# Sheet1.net
KiCad netlist of a schematic drawn in Altium Designer
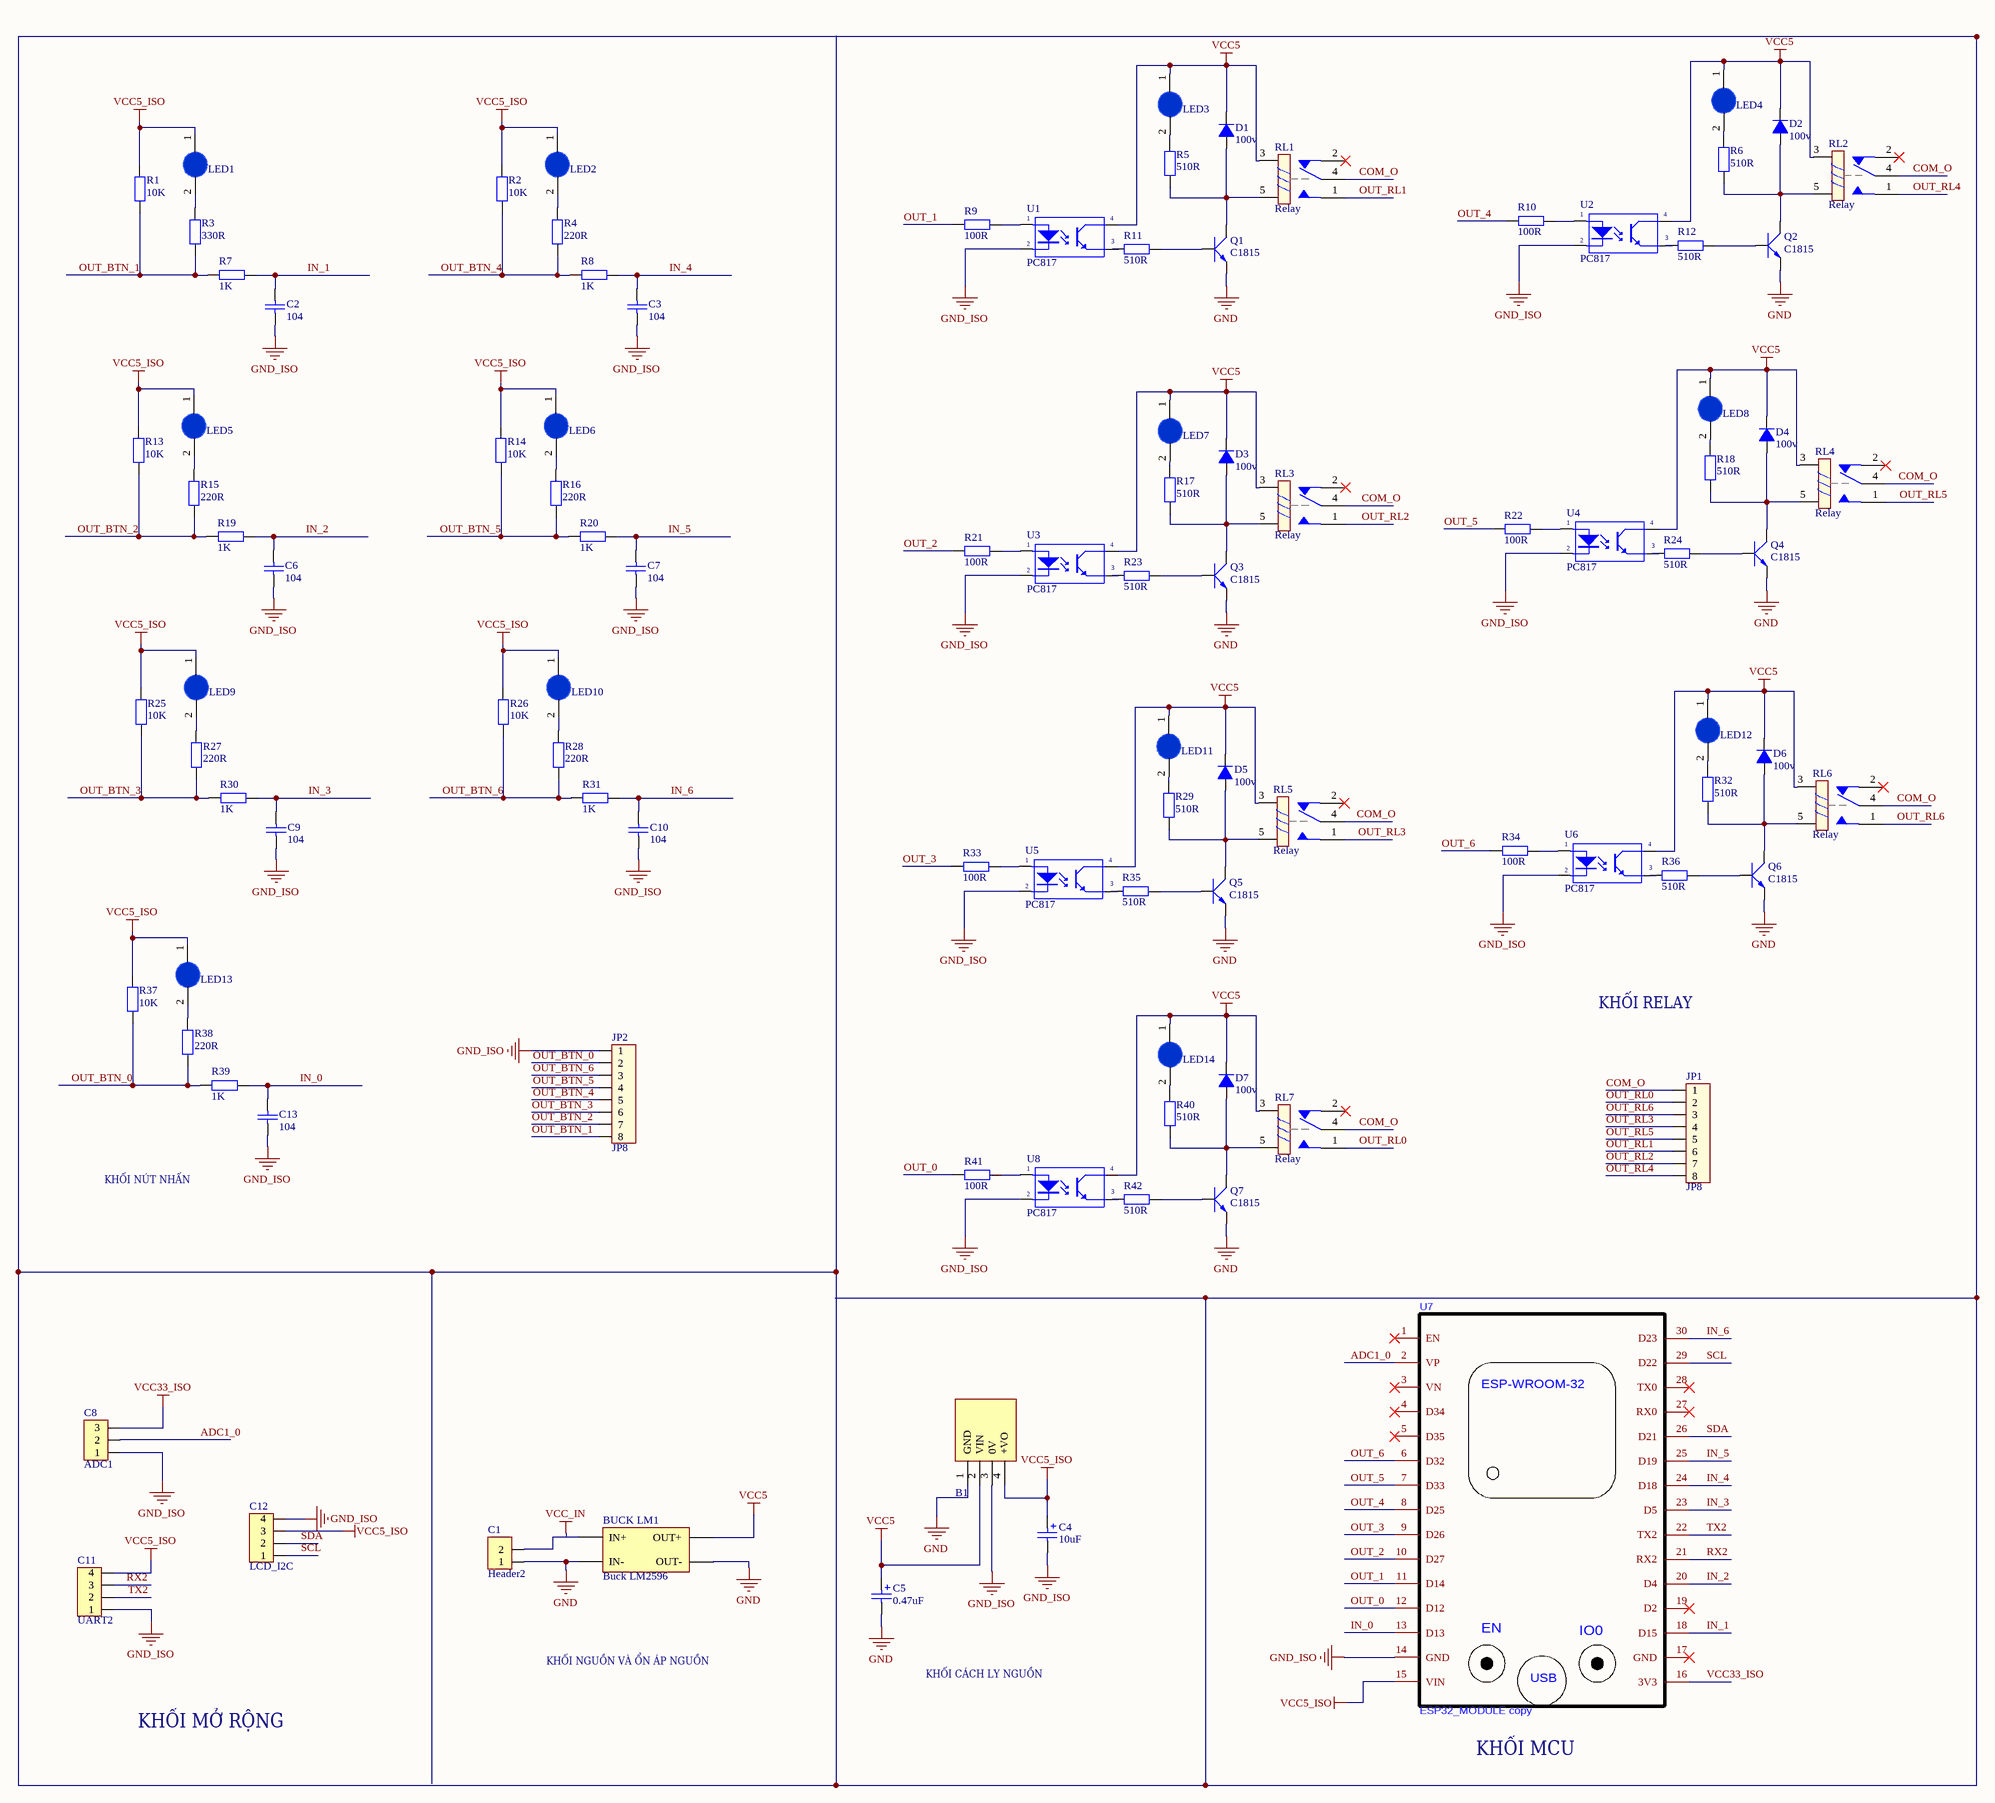
[diagram p0: Sheet1.SchDoc]

(export (version "E")
  (design (tool "Eeschema 10.0.6"))
  (components
    (comp (ref "B1")
      (value "B0505S1W")
      (footprint "B0505S1W")
      (description "Power Supply")
      (fields (field (name "MANUFACTURER_PART_NUMBER") "B0505S-1W"))
      (libsource (lib "myLib_v1") (part "B0505S1W"))
    )
    (comp (ref "BUCK LM1")
      (value "Buck LM2596")
      (footprint "BUCK LM2596")
      (libsource (lib "myLib_v1") (part "Buck LM2596"))
    )
    (comp (ref "C1")
      (value "Header2")
      (footprint "Header2")
      (description "Header IDC, 2 x 1 Pin Vertical 2.54mm Pitch (Non-Boxed, Male)")
      (fields
        (field (name "MANUFACTURER") "Würth Elektronik eiSos GmbH")
        (field (name "PARTNO") "613002143121")
        (field (name "CREATED BY") "Karrer Zheng")
      )
      (libsource (lib "myLib_v1") (part "Header2"))
    )
    (comp (ref "C2")
      (value "104")
      (footprint "tu gom")
      (description "Cắm")
      (libsource (lib "Altium_Lib_by_KhueNguyenCreator") (part "Tu gom 104 50V"))
    )
    (comp (ref "C3")
      (value "104")
      (footprint "tu gom")
      (description "Cắm")
      (libsource (lib "Altium_Lib_by_KhueNguyenCreator") (part "Tu gom 104 50V"))
    )
    (comp (ref "C4")
      (value "10uF")
      (footprint "CP2/5")
      (description "Polarized Capacitor (Surface Mount)")
      (fields (field (name "Comment") "Cap Pol3") (field (name "PUBLISHER") "Altium Limited"))
      (libsource (lib "myLib_v1") (part "Cap Pol3"))
    )
    (comp (ref "C5")
      (value "0.47uF")
      (footprint "CP2/5")
      (description "Polarized Capacitor (Surface Mount)")
      (fields (field (name "Comment") "Cap Pol3") (field (name "PUBLISHER") "Altium Limited"))
      (libsource (lib "myLib_v1") (part "Cap Pol3"))
    )
    (comp (ref "C6")
      (value "104")
      (footprint "tu gom")
      (description "Cắm")
      (libsource (lib "Altium_Lib_by_KhueNguyenCreator") (part "Tu gom 104 50V"))
    )
    (comp (ref "C7")
      (value "104")
      (footprint "tu gom")
      (description "Cắm")
      (libsource (lib "Altium_Lib_by_KhueNguyenCreator") (part "Tu gom 104 50V"))
    )
    (comp (ref "C8")
      (value "ADC1")
      (footprint "Header3")
      (description "Header IDC, 3 x 1 Pin Vertical 2.54mm Pitch (Non-Boxed, Male)")
      (fields
        (field (name "MANUFACTURER") "Würth Elektronik eiSos GmbH")
        (field (name "PARTNO") "613002143121")
        (field (name "CREATED BY") "Karrer Zheng")
      )
      (libsource (lib "myLib_v1") (part "Header3"))
    )
    (comp (ref "C9")
      (value "104")
      (footprint "tu gom")
      (description "Cắm")
      (libsource (lib "Altium_Lib_by_KhueNguyenCreator") (part "Tu gom 104 50V"))
    )
    (comp (ref "C10")
      (value "104")
      (footprint "tu gom")
      (description "Cắm")
      (libsource (lib "Altium_Lib_by_KhueNguyenCreator") (part "Tu gom 104 50V"))
    )
    (comp (ref "C11")
      (value "UART2")
      (footprint "Header4")
      (description "Header IDC, 4 x 1 Pin Vertical 2.54mm Pitch (Non-Boxed, Male)")
      (fields
        (field (name "MANUFACTURER") "Würth Elektronik eiSos GmbH")
        (field (name "PARTNO") "613002143121")
        (field (name "CREATED BY") "Karrer Zheng")
      )
      (libsource (lib "myLib_v1") (part "Header4"))
    )
    (comp (ref "C12")
      (value "LCD_I2C")
      (footprint "Header4")
      (description "Header IDC, 4 x 1 Pin Vertical 2.54mm Pitch (Non-Boxed, Male)")
      (fields
        (field (name "MANUFACTURER") "Würth Elektronik eiSos GmbH")
        (field (name "PARTNO") "613002143121")
        (field (name "CREATED BY") "Karrer Zheng")
      )
      (libsource (lib "myLib_v1") (part "Header4"))
    )
    (comp (ref "C13")
      (value "104")
      (footprint "tu gom")
      (description "Cắm")
      (libsource (lib "Altium_Lib_by_KhueNguyenCreator") (part "Tu gom 104 50V"))
    )
    (comp (ref "D1")
      (value "100v")
      (footprint "DIODE 0.5A")
      (description "Cắm")
      (libsource (lib "Altium_Lib_by_KhueNguyenCreator") (part "Diode 1N4148"))
    )
    (comp (ref "D2")
      (value "100v")
      (footprint "DIODE 0.5A")
      (description "Cắm")
      (libsource (lib "Altium_Lib_by_KhueNguyenCreator") (part "Diode 1N4148"))
    )
    (comp (ref "D3")
      (value "100v")
      (footprint "DIODE 0.5A")
      (description "Cắm")
      (libsource (lib "Altium_Lib_by_KhueNguyenCreator") (part "Diode 1N4148"))
    )
    (comp (ref "D4")
      (value "100v")
      (footprint "DIODE 0.5A")
      (description "Cắm")
      (libsource (lib "Altium_Lib_by_KhueNguyenCreator") (part "Diode 1N4148"))
    )
    (comp (ref "D5")
      (value "100v")
      (footprint "DIODE 0.5A")
      (description "Cắm")
      (libsource (lib "Altium_Lib_by_KhueNguyenCreator") (part "Diode 1N4148"))
    )
    (comp (ref "D6")
      (value "100v")
      (footprint "DIODE 0.5A")
      (description "Cắm")
      (libsource (lib "Altium_Lib_by_KhueNguyenCreator") (part "Diode 1N4148"))
    )
    (comp (ref "D7")
      (value "100v")
      (footprint "DIODE 0.5A")
      (description "Cắm")
      (libsource (lib "Altium_Lib_by_KhueNguyenCreator") (part "Diode 1N4148"))
    )
    (comp (ref "JP1")
      (value "JP8")
      (footprint "Header8")
      (description "Connector 8")
      (libsource (lib "myLib_v1") (part "Header8"))
    )
    (comp (ref "JP2")
      (value "JP8")
      (footprint "Header8")
      (description "Connector 8")
      (libsource (lib "myLib_v1") (part "Header8"))
    )
    (comp (ref "LED1")
      (value "LED 3mm")
      (footprint "LED-3MM-BLUE")
      (description "Cắm")
      (libsource (lib "myLib_v1") (part "LED 3mm Xanh Duong"))
    )
    (comp (ref "LED2")
      (value "LED 3mm")
      (footprint "LED-3MM-BLUE")
      (description "Cắm")
      (libsource (lib "myLib_v1") (part "LED 3mm Xanh Duong"))
    )
    (comp (ref "LED3")
      (value "LED 3mm")
      (footprint "LED-3MM-BLUE")
      (description "Cắm")
      (libsource (lib "myLib_v1") (part "LED 3mm Xanh Duong"))
    )
    (comp (ref "LED4")
      (value "LED 3mm")
      (footprint "LED-3MM-BLUE")
      (description "Cắm")
      (libsource (lib "myLib_v1") (part "LED 3mm Xanh Duong"))
    )
    (comp (ref "LED5")
      (value "LED 3mm")
      (footprint "LED-3MM-BLUE")
      (description "Cắm")
      (libsource (lib "myLib_v1") (part "LED 3mm Xanh Duong"))
    )
    (comp (ref "LED6")
      (value "LED 3mm")
      (footprint "LED-3MM-BLUE")
      (description "Cắm")
      (libsource (lib "myLib_v1") (part "LED 3mm Xanh Duong"))
    )
    (comp (ref "LED7")
      (value "LED 3mm")
      (footprint "LED-3MM-BLUE")
      (description "Cắm")
      (libsource (lib "myLib_v1") (part "LED 3mm Xanh Duong"))
    )
    (comp (ref "LED8")
      (value "LED 3mm")
      (footprint "LED-3MM-BLUE")
      (description "Cắm")
      (libsource (lib "myLib_v1") (part "LED 3mm Xanh Duong"))
    )
    (comp (ref "LED9")
      (value "LED 3mm")
      (footprint "LED-3MM-BLUE")
      (description "Cắm")
      (libsource (lib "myLib_v1") (part "LED 3mm Xanh Duong"))
    )
    (comp (ref "LED10")
      (value "LED 3mm")
      (footprint "LED-3MM-BLUE")
      (description "Cắm")
      (libsource (lib "myLib_v1") (part "LED 3mm Xanh Duong"))
    )
    (comp (ref "LED11")
      (value "LED 3mm")
      (footprint "LED-3MM-BLUE")
      (description "Cắm")
      (libsource (lib "myLib_v1") (part "LED 3mm Xanh Duong"))
    )
    (comp (ref "LED12")
      (value "LED 3mm")
      (footprint "LED-3MM-BLUE")
      (description "Cắm")
      (libsource (lib "myLib_v1") (part "LED 3mm Xanh Duong"))
    )
    (comp (ref "LED13")
      (value "LED 3mm")
      (footprint "LED-3MM-BLUE")
      (description "Cắm")
      (libsource (lib "myLib_v1") (part "LED 3mm Xanh Duong"))
    )
    (comp (ref "LED14")
      (value "LED 3mm")
      (footprint "LED-3MM-BLUE")
      (description "Cắm")
      (libsource (lib "myLib_v1") (part "LED 3mm Xanh Duong"))
    )
    (comp (ref "Q1")
      (value "C1815")
      (footprint "C1815_cam")
      (description "NPN 600mW, ECB")
      (libsource (lib "myLib_v1") (part "C1815"))
    )
    (comp (ref "Q2")
      (value "C1815")
      (footprint "C1815_cam")
      (description "NPN 600mW, ECB")
      (libsource (lib "myLib_v1") (part "C1815"))
    )
    (comp (ref "Q3")
      (value "C1815")
      (footprint "C1815_cam")
      (description "NPN 600mW, ECB")
      (libsource (lib "myLib_v1") (part "C1815"))
    )
    (comp (ref "Q4")
      (value "C1815")
      (footprint "C1815_cam")
      (description "NPN 600mW, ECB")
      (libsource (lib "myLib_v1") (part "C1815"))
    )
    (comp (ref "Q5")
      (value "C1815")
      (footprint "C1815_cam")
      (description "NPN 600mW, ECB")
      (libsource (lib "myLib_v1") (part "C1815"))
    )
    (comp (ref "Q6")
      (value "C1815")
      (footprint "C1815_cam")
      (description "NPN 600mW, ECB")
      (libsource (lib "myLib_v1") (part "C1815"))
    )
    (comp (ref "Q7")
      (value "C1815")
      (footprint "C1815_cam")
      (description "NPN 600mW, ECB")
      (libsource (lib "myLib_v1") (part "C1815"))
    )
    (comp (ref "R1")
      (value "10K")
      (footprint "R1/4W")
      (description "Resistor 1/4W")
      (libsource (lib "myLib_v1") (part "R1/4W"))
    )
    (comp (ref "R2")
      (value "10K")
      (footprint "R1/4W")
      (description "Resistor 1/4W")
      (libsource (lib "myLib_v1") (part "R1/4W"))
    )
    (comp (ref "R3")
      (value "330R")
      (footprint "R1/4W")
      (description "Resistor 1/4W")
      (libsource (lib "myLib_v1") (part "R1/4W"))
    )
    (comp (ref "R4")
      (value "220R")
      (footprint "R1/4W")
      (description "Resistor 1/4W")
      (libsource (lib "myLib_v1") (part "R1/4W"))
    )
    (comp (ref "R5")
      (value "510R")
      (footprint "R1/4W")
      (description "Resistor 1/4W")
      (libsource (lib "myLib_v1") (part "R1/4W"))
    )
    (comp (ref "R6")
      (value "510R")
      (footprint "R1/4W")
      (description "Resistor 1/4W")
      (libsource (lib "myLib_v1") (part "R1/4W"))
    )
    (comp (ref "R7")
      (value "1K")
      (footprint "R1/4W")
      (description "Resistor 1/4W")
      (libsource (lib "myLib_v1") (part "R1/4W"))
    )
    (comp (ref "R8")
      (value "1K")
      (footprint "R1/4W")
      (description "Resistor 1/4W")
      (libsource (lib "myLib_v1") (part "R1/4W"))
    )
    (comp (ref "R9")
      (value "100R")
      (footprint "R1/4W")
      (description "Resistor 1/4W")
      (libsource (lib "myLib_v1") (part "R1/4W"))
    )
    (comp (ref "R10")
      (value "100R")
      (footprint "R1/4W")
      (description "Resistor 1/4W")
      (libsource (lib "myLib_v1") (part "R1/4W"))
    )
    (comp (ref "R11")
      (value "510R")
      (footprint "R1/4W")
      (description "Resistor 1/4W")
      (libsource (lib "myLib_v1") (part "R1/4W"))
    )
    (comp (ref "R12")
      (value "510R")
      (footprint "R1/4W")
      (description "Resistor 1/4W")
      (libsource (lib "myLib_v1") (part "R1/4W"))
    )
    (comp (ref "R13")
      (value "10K")
      (footprint "R1/4W")
      (description "Resistor 1/4W")
      (libsource (lib "myLib_v1") (part "R1/4W"))
    )
    (comp (ref "R14")
      (value "10K")
      (footprint "R1/4W")
      (description "Resistor 1/4W")
      (libsource (lib "myLib_v1") (part "R1/4W"))
    )
    (comp (ref "R15")
      (value "220R")
      (footprint "R1/4W")
      (description "Resistor 1/4W")
      (libsource (lib "myLib_v1") (part "R1/4W"))
    )
    (comp (ref "R16")
      (value "220R")
      (footprint "R1/4W")
      (description "Resistor 1/4W")
      (libsource (lib "myLib_v1") (part "R1/4W"))
    )
    (comp (ref "R17")
      (value "510R")
      (footprint "R1/4W")
      (description "Resistor 1/4W")
      (libsource (lib "myLib_v1") (part "R1/4W"))
    )
    (comp (ref "R18")
      (value "510R")
      (footprint "R1/4W")
      (description "Resistor 1/4W")
      (libsource (lib "myLib_v1") (part "R1/4W"))
    )
    (comp (ref "R19")
      (value "1K")
      (footprint "R1/4W")
      (description "Resistor 1/4W")
      (libsource (lib "myLib_v1") (part "R1/4W"))
    )
    (comp (ref "R20")
      (value "1K")
      (footprint "R1/4W")
      (description "Resistor 1/4W")
      (libsource (lib "myLib_v1") (part "R1/4W"))
    )
    (comp (ref "R21")
      (value "100R")
      (footprint "R1/4W")
      (description "Resistor 1/4W")
      (libsource (lib "myLib_v1") (part "R1/4W"))
    )
    (comp (ref "R22")
      (value "100R")
      (footprint "R1/4W")
      (description "Resistor 1/4W")
      (libsource (lib "myLib_v1") (part "R1/4W"))
    )
    (comp (ref "R23")
      (value "510R")
      (footprint "R1/4W")
      (description "Resistor 1/4W")
      (libsource (lib "myLib_v1") (part "R1/4W"))
    )
    (comp (ref "R24")
      (value "510R")
      (footprint "R1/4W")
      (description "Resistor 1/4W")
      (libsource (lib "myLib_v1") (part "R1/4W"))
    )
    (comp (ref "R25")
      (value "10K")
      (footprint "R1/4W")
      (description "Resistor 1/4W")
      (libsource (lib "myLib_v1") (part "R1/4W"))
    )
    (comp (ref "R26")
      (value "10K")
      (footprint "R1/4W")
      (description "Resistor 1/4W")
      (libsource (lib "myLib_v1") (part "R1/4W"))
    )
    (comp (ref "R27")
      (value "220R")
      (footprint "R1/4W")
      (description "Resistor 1/4W")
      (libsource (lib "myLib_v1") (part "R1/4W"))
    )
    (comp (ref "R28")
      (value "220R")
      (footprint "R1/4W")
      (description "Resistor 1/4W")
      (libsource (lib "myLib_v1") (part "R1/4W"))
    )
    (comp (ref "R29")
      (value "510R")
      (footprint "R1/4W")
      (description "Resistor 1/4W")
      (libsource (lib "myLib_v1") (part "R1/4W"))
    )
    (comp (ref "R30")
      (value "1K")
      (footprint "R1/4W")
      (description "Resistor 1/4W")
      (libsource (lib "myLib_v1") (part "R1/4W"))
    )
    (comp (ref "R31")
      (value "1K")
      (footprint "R1/4W")
      (description "Resistor 1/4W")
      (libsource (lib "myLib_v1") (part "R1/4W"))
    )
    (comp (ref "R32")
      (value "510R")
      (footprint "R1/4W")
      (description "Resistor 1/4W")
      (libsource (lib "myLib_v1") (part "R1/4W"))
    )
    (comp (ref "R33")
      (value "100R")
      (footprint "R1/4W")
      (description "Resistor 1/4W")
      (libsource (lib "myLib_v1") (part "R1/4W"))
    )
    (comp (ref "R34")
      (value "100R")
      (footprint "R1/4W")
      (description "Resistor 1/4W")
      (libsource (lib "myLib_v1") (part "R1/4W"))
    )
    (comp (ref "R35")
      (value "510R")
      (footprint "R1/4W")
      (description "Resistor 1/4W")
      (libsource (lib "myLib_v1") (part "R1/4W"))
    )
    (comp (ref "R36")
      (value "510R")
      (footprint "R1/4W")
      (description "Resistor 1/4W")
      (libsource (lib "myLib_v1") (part "R1/4W"))
    )
    (comp (ref "R37")
      (value "10K")
      (footprint "R1/4W")
      (description "Resistor 1/4W")
      (libsource (lib "myLib_v1") (part "R1/4W"))
    )
    (comp (ref "R38")
      (value "220R")
      (footprint "R1/4W")
      (description "Resistor 1/4W")
      (libsource (lib "myLib_v1") (part "R1/4W"))
    )
    (comp (ref "R39")
      (value "1K")
      (footprint "R1/4W")
      (description "Resistor 1/4W")
      (libsource (lib "myLib_v1") (part "R1/4W"))
    )
    (comp (ref "R40")
      (value "510R")
      (footprint "R1/4W")
      (description "Resistor 1/4W")
      (libsource (lib "myLib_v1") (part "R1/4W"))
    )
    (comp (ref "R41")
      (value "100R")
      (footprint "R1/4W")
      (description "Resistor 1/4W")
      (libsource (lib "myLib_v1") (part "R1/4W"))
    )
    (comp (ref "R42")
      (value "510R")
      (footprint "R1/4W")
      (description "Resistor 1/4W")
      (libsource (lib "myLib_v1") (part "R1/4W"))
    )
    (comp (ref "RL1")
      (value "Relay")
      (footprint "RELAY_SRA_05VDC_SL_C")
      (description "Relay 5 Chan")
      (libsource (lib "myLib_v1") (part "RL_SRA-05VDC-SL-C"))
    )
    (comp (ref "RL2")
      (value "Relay")
      (footprint "RELAY_SRA_05VDC_SL_C")
      (description "Relay 5 Chan")
      (libsource (lib "myLib_v1") (part "RL_SRA-05VDC-SL-C"))
    )
    (comp (ref "RL3")
      (value "Relay")
      (footprint "RELAY_SRA_05VDC_SL_C")
      (description "Relay 5 Chan")
      (libsource (lib "myLib_v1") (part "RL_SRA-05VDC-SL-C"))
    )
    (comp (ref "RL4")
      (value "Relay")
      (footprint "RELAY_SRA_05VDC_SL_C")
      (description "Relay 5 Chan")
      (libsource (lib "myLib_v1") (part "RL_SRA-05VDC-SL-C"))
    )
    (comp (ref "RL5")
      (value "Relay")
      (footprint "RELAY_SRA_05VDC_SL_C")
      (description "Relay 5 Chan")
      (libsource (lib "myLib_v1") (part "RL_SRA-05VDC-SL-C"))
    )
    (comp (ref "RL6")
      (value "Relay")
      (footprint "RELAY_SRA_05VDC_SL_C")
      (description "Relay 5 Chan")
      (libsource (lib "myLib_v1") (part "RL_SRA-05VDC-SL-C"))
    )
    (comp (ref "RL7")
      (value "Relay")
      (footprint "RELAY_SRA_05VDC_SL_C")
      (description "Relay 5 Chan")
      (libsource (lib "myLib_v1") (part "RL_SRA-05VDC-SL-C"))
    )
    (comp (ref "U1")
      (value "PC817")
      (footprint "DIP4/W0.3")
      (description "Single Opto")
      (libsource (lib "myLib_v1") (part "PC817"))
    )
    (comp (ref "U2")
      (value "PC817")
      (footprint "DIP4/W0.3")
      (description "Single Opto")
      (libsource (lib "myLib_v1") (part "PC817"))
    )
    (comp (ref "U3")
      (value "PC817")
      (footprint "DIP4/W0.3")
      (description "Single Opto")
      (libsource (lib "myLib_v1") (part "PC817"))
    )
    (comp (ref "U4")
      (value "PC817")
      (footprint "DIP4/W0.3")
      (description "Single Opto")
      (libsource (lib "myLib_v1") (part "PC817"))
    )
    (comp (ref "U5")
      (value "PC817")
      (footprint "DIP4/W0.3")
      (description "Single Opto")
      (libsource (lib "myLib_v1") (part "PC817"))
    )
    (comp (ref "U6")
      (value "PC817")
      (footprint "DIP4/W0.3")
      (description "Single Opto")
      (libsource (lib "myLib_v1") (part "PC817"))
    )
    (comp (ref "U7")
      (value "ESP32_MODULE copy")
      (footprint "ESP32-WIFIMODULE-FOOTPRINT")
      (libsource (lib "myLib_v1") (part "ESP32_MODULE copy"))
    )
    (comp (ref "U8")
      (value "PC817")
      (footprint "DIP4/W0.3")
      (description "Single Opto")
      (libsource (lib "myLib_v1") (part "PC817"))
    )
  )
  (nets
    (net (code "1") (name "/ADC1_0") (class "Default")
      (node (ref "C8") (pin "2") (pinfunction "2_2") (pintype "passive"))
      (node (ref "U7") (pin "2") (pinfunction "VP_2") (pintype "passive"))
    )
    (net (code "2") (name "/COM_O") (class "Default")
      (node (ref "JP1") (pin "1") (pinfunction "1_1") (pintype "passive"))
      (node (ref "RL1") (pin "4") (pinfunction "4_4") (pintype "passive"))
      (node (ref "RL2") (pin "4") (pinfunction "4_4") (pintype "passive"))
      (node (ref "RL3") (pin "4") (pinfunction "4_4") (pintype "passive"))
      (node (ref "RL4") (pin "4") (pinfunction "4_4") (pintype "passive"))
      (node (ref "RL5") (pin "4") (pinfunction "4_4") (pintype "passive"))
      (node (ref "RL6") (pin "4") (pinfunction "4_4") (pintype "passive"))
      (node (ref "RL7") (pin "4") (pinfunction "4_4") (pintype "passive"))
    )
    (net (code "3") (name "/IN_0") (class "Default")
      (node (ref "C13") (pin "1") (pinfunction "1_1") (pintype "passive"))
      (node (ref "R39") (pin "1") (pinfunction "1_1") (pintype "passive"))
      (node (ref "U7") (pin "13") (pinfunction "D13_13") (pintype "passive"))
    )
    (net (code "4") (name "/IN_1") (class "Default")
      (node (ref "C2") (pin "1") (pinfunction "1_1") (pintype "passive"))
      (node (ref "R7") (pin "1") (pinfunction "1_1") (pintype "passive"))
      (node (ref "U7") (pin "18") (pinfunction "D15_18") (pintype "passive"))
    )
    (net (code "5") (name "/IN_2") (class "Default")
      (node (ref "C6") (pin "1") (pinfunction "1_1") (pintype "passive"))
      (node (ref "R19") (pin "1") (pinfunction "1_1") (pintype "passive"))
      (node (ref "U7") (pin "20") (pinfunction "D4_20") (pintype "passive"))
    )
    (net (code "6") (name "/IN_3") (class "Default")
      (node (ref "C9") (pin "1") (pinfunction "1_1") (pintype "passive"))
      (node (ref "R30") (pin "1") (pinfunction "1_1") (pintype "passive"))
      (node (ref "U7") (pin "23") (pinfunction "D5_23") (pintype "passive"))
    )
    (net (code "7") (name "/IN_4") (class "Default")
      (node (ref "C3") (pin "1") (pinfunction "1_1") (pintype "passive"))
      (node (ref "R8") (pin "1") (pinfunction "1_1") (pintype "passive"))
      (node (ref "U7") (pin "24") (pinfunction "D18_24") (pintype "passive"))
    )
    (net (code "8") (name "/IN_5") (class "Default")
      (node (ref "C7") (pin "1") (pinfunction "1_1") (pintype "passive"))
      (node (ref "R20") (pin "1") (pinfunction "1_1") (pintype "passive"))
      (node (ref "U7") (pin "25") (pinfunction "D19_25") (pintype "passive"))
    )
    (net (code "9") (name "/IN_6") (class "Default")
      (node (ref "C10") (pin "1") (pinfunction "1_1") (pintype "passive"))
      (node (ref "R31") (pin "1") (pinfunction "1_1") (pintype "passive"))
      (node (ref "U7") (pin "30") (pinfunction "D23_30") (pintype "passive"))
    )
    (net (code "10") (name "/OUT_0") (class "Default")
      (node (ref "R41") (pin "1") (pinfunction "1_1") (pintype "passive"))
      (node (ref "U7") (pin "12") (pinfunction "D12_12") (pintype "passive"))
    )
    (net (code "11") (name "/OUT_1") (class "Default")
      (node (ref "R9") (pin "1") (pinfunction "1_1") (pintype "passive"))
      (node (ref "U7") (pin "11") (pinfunction "D14_11") (pintype "passive"))
    )
    (net (code "12") (name "/OUT_2") (class "Default")
      (node (ref "R21") (pin "1") (pinfunction "1_1") (pintype "passive"))
      (node (ref "U7") (pin "10") (pinfunction "D27_10") (pintype "passive"))
    )
    (net (code "13") (name "/OUT_3") (class "Default")
      (node (ref "R33") (pin "1") (pinfunction "1_1") (pintype "passive"))
      (node (ref "U7") (pin "9") (pinfunction "D26_9") (pintype "passive"))
    )
    (net (code "14") (name "/OUT_4") (class "Default")
      (node (ref "R10") (pin "1") (pinfunction "1_1") (pintype "passive"))
      (node (ref "U7") (pin "8") (pinfunction "D25_8") (pintype "passive"))
    )
    (net (code "15") (name "/OUT_5") (class "Default")
      (node (ref "R22") (pin "1") (pinfunction "1_1") (pintype "passive"))
      (node (ref "U7") (pin "7") (pinfunction "D33_7") (pintype "passive"))
    )
    (net (code "16") (name "/OUT_6") (class "Default")
      (node (ref "R34") (pin "1") (pinfunction "1_1") (pintype "passive"))
      (node (ref "U7") (pin "6") (pinfunction "D32_6") (pintype "passive"))
    )
    (net (code "17") (name "/OUT_BTN_0") (class "Default")
      (node (ref "JP2") (pin "2") (pinfunction "2_2") (pintype "passive"))
      (node (ref "R37") (pin "1") (pinfunction "1_1") (pintype "passive"))
      (node (ref "R38") (pin "1") (pinfunction "1_1") (pintype "passive"))
      (node (ref "R39") (pin "2") (pinfunction "2_2") (pintype "passive"))
    )
    (net (code "18") (name "/OUT_BTN_1") (class "Default")
      (node (ref "JP2") (pin "8") (pinfunction "8_8") (pintype "passive"))
      (node (ref "R1") (pin "1") (pinfunction "1_1") (pintype "passive"))
      (node (ref "R3") (pin "1") (pinfunction "1_1") (pintype "passive"))
      (node (ref "R7") (pin "2") (pinfunction "2_2") (pintype "passive"))
    )
    (net (code "19") (name "/OUT_BTN_2") (class "Default")
      (node (ref "JP2") (pin "7") (pinfunction "7_7") (pintype "passive"))
      (node (ref "R13") (pin "1") (pinfunction "1_1") (pintype "passive"))
      (node (ref "R15") (pin "1") (pinfunction "1_1") (pintype "passive"))
      (node (ref "R19") (pin "2") (pinfunction "2_2") (pintype "passive"))
    )
    (net (code "20") (name "/OUT_BTN_3") (class "Default")
      (node (ref "JP2") (pin "6") (pinfunction "6_6") (pintype "passive"))
      (node (ref "R25") (pin "1") (pinfunction "1_1") (pintype "passive"))
      (node (ref "R27") (pin "1") (pinfunction "1_1") (pintype "passive"))
      (node (ref "R30") (pin "2") (pinfunction "2_2") (pintype "passive"))
    )
    (net (code "21") (name "/OUT_BTN_4") (class "Default")
      (node (ref "JP2") (pin "5") (pinfunction "5_5") (pintype "passive"))
      (node (ref "R2") (pin "1") (pinfunction "1_1") (pintype "passive"))
      (node (ref "R4") (pin "1") (pinfunction "1_1") (pintype "passive"))
      (node (ref "R8") (pin "2") (pinfunction "2_2") (pintype "passive"))
    )
    (net (code "22") (name "/OUT_BTN_5") (class "Default")
      (node (ref "JP2") (pin "4") (pinfunction "4_4") (pintype "passive"))
      (node (ref "R14") (pin "1") (pinfunction "1_1") (pintype "passive"))
      (node (ref "R16") (pin "1") (pinfunction "1_1") (pintype "passive"))
      (node (ref "R20") (pin "2") (pinfunction "2_2") (pintype "passive"))
    )
    (net (code "23") (name "/OUT_BTN_6") (class "Default")
      (node (ref "JP2") (pin "3") (pinfunction "3_3") (pintype "passive"))
      (node (ref "R26") (pin "1") (pinfunction "1_1") (pintype "passive"))
      (node (ref "R28") (pin "1") (pinfunction "1_1") (pintype "passive"))
      (node (ref "R31") (pin "2") (pinfunction "2_2") (pintype "passive"))
    )
    (net (code "24") (name "/OUT_RL0") (class "Default")
      (node (ref "JP1") (pin "2") (pinfunction "2_2") (pintype "passive"))
      (node (ref "RL7") (pin "1") (pinfunction "1_1") (pintype "passive"))
    )
    (net (code "25") (name "/OUT_RL1") (class "Default")
      (node (ref "JP1") (pin "6") (pinfunction "6_6") (pintype "passive"))
      (node (ref "RL1") (pin "1") (pinfunction "1_1") (pintype "passive"))
    )
    (net (code "26") (name "/OUT_RL2") (class "Default")
      (node (ref "JP1") (pin "7") (pinfunction "7_7") (pintype "passive"))
      (node (ref "RL3") (pin "1") (pinfunction "1_1") (pintype "passive"))
    )
    (net (code "27") (name "/OUT_RL3") (class "Default")
      (node (ref "JP1") (pin "4") (pinfunction "4_4") (pintype "passive"))
      (node (ref "RL5") (pin "1") (pinfunction "1_1") (pintype "passive"))
    )
    (net (code "28") (name "/OUT_RL4") (class "Default")
      (node (ref "JP1") (pin "8") (pinfunction "8_8") (pintype "passive"))
      (node (ref "RL2") (pin "1") (pinfunction "1_1") (pintype "passive"))
    )
    (net (code "29") (name "/OUT_RL5") (class "Default")
      (node (ref "JP1") (pin "5") (pinfunction "5_5") (pintype "passive"))
      (node (ref "RL4") (pin "1") (pinfunction "1_1") (pintype "passive"))
    )
    (net (code "30") (name "/OUT_RL6") (class "Default")
      (node (ref "JP1") (pin "3") (pinfunction "3_3") (pintype "passive"))
      (node (ref "RL6") (pin "1") (pinfunction "1_1") (pintype "passive"))
    )
    (net (code "31") (name "/RX2") (class "Default")
      (node (ref "C11") (pin "3") (pinfunction "3_3") (pintype "passive"))
      (node (ref "U7") (pin "21") (pinfunction "RX2_21") (pintype "passive"))
    )
    (net (code "32") (name "/SCL") (class "Default")
      (node (ref "C12") (pin "1") (pinfunction "1_1") (pintype "passive"))
      (node (ref "U7") (pin "29") (pinfunction "D22_29") (pintype "passive"))
    )
    (net (code "33") (name "/SDA") (class "Default")
      (node (ref "C12") (pin "2") (pinfunction "2_2") (pintype "passive"))
      (node (ref "U7") (pin "26") (pinfunction "D21_26") (pintype "passive"))
    )
    (net (code "34") (name "/TX2") (class "Default")
      (node (ref "C11") (pin "2") (pinfunction "2_2") (pintype "passive"))
      (node (ref "U7") (pin "22") (pinfunction "TX2_22") (pintype "passive"))
    )
    (net (code "35") (name "GND") (class "Default")
      (node (ref "B1") (pin "1") (pinfunction "GND_1") (pintype "passive"))
      (node (ref "BUCK LM1") (pin "2") (pinfunction "IN-_2") (pintype "passive"))
      (node (ref "BUCK LM1") (pin "3") (pinfunction "OUT-_3") (pintype "passive"))
      (node (ref "C1") (pin "1") (pinfunction "1_1") (pintype "passive"))
      (node (ref "C5") (pin "2") (pinfunction "2_2") (pintype "passive"))
      (node (ref "Q1") (pin "1") (pinfunction "E_1") (pintype "passive"))
      (node (ref "Q2") (pin "1") (pinfunction "E_1") (pintype "passive"))
      (node (ref "Q3") (pin "1") (pinfunction "E_1") (pintype "passive"))
      (node (ref "Q4") (pin "1") (pinfunction "E_1") (pintype "passive"))
      (node (ref "Q5") (pin "1") (pinfunction "E_1") (pintype "passive"))
      (node (ref "Q6") (pin "1") (pinfunction "E_1") (pintype "passive"))
      (node (ref "Q7") (pin "1") (pinfunction "E_1") (pintype "passive"))
    )
    (net (code "36") (name "GND_ISO") (class "Default")
      (node (ref "B1") (pin "3") (pinfunction "0V_3") (pintype "passive"))
      (node (ref "C10") (pin "2") (pinfunction "2_2") (pintype "passive"))
      (node (ref "C11") (pin "1") (pinfunction "1_1") (pintype "passive"))
      (node (ref "C12") (pin "4") (pinfunction "4_4") (pintype "passive"))
      (node (ref "C13") (pin "2") (pinfunction "2_2") (pintype "passive"))
      (node (ref "C2") (pin "2") (pinfunction "2_2") (pintype "passive"))
      (node (ref "C3") (pin "2") (pinfunction "2_2") (pintype "passive"))
      (node (ref "C4") (pin "2") (pinfunction "2_2") (pintype "passive"))
      (node (ref "C6") (pin "2") (pinfunction "2_2") (pintype "passive"))
      (node (ref "C7") (pin "2") (pinfunction "2_2") (pintype "passive"))
      (node (ref "C8") (pin "1") (pinfunction "1_1") (pintype "passive"))
      (node (ref "C9") (pin "2") (pinfunction "2_2") (pintype "passive"))
      (node (ref "JP2") (pin "1") (pinfunction "1_1") (pintype "passive"))
      (node (ref "U1") (pin "2") (pinfunction "K_2") (pintype "passive"))
      (node (ref "U2") (pin "2") (pinfunction "K_2") (pintype "passive"))
      (node (ref "U3") (pin "2") (pinfunction "K_2") (pintype "passive"))
      (node (ref "U4") (pin "2") (pinfunction "K_2") (pintype "passive"))
      (node (ref "U5") (pin "2") (pinfunction "K_2") (pintype "passive"))
      (node (ref "U6") (pin "2") (pinfunction "K_2") (pintype "passive"))
      (node (ref "U7") (pin "14") (pinfunction "GND_14") (pintype "passive"))
      (node (ref "U8") (pin "2") (pinfunction "K_2") (pintype "passive"))
    )
    (net (code "37") (name "Net-(D1-A)") (class "Default")
      (node (ref "D1") (pin "1") (pinfunction "A_1") (pintype "passive"))
      (node (ref "Q1") (pin "2") (pinfunction "C_2") (pintype "passive"))
      (node (ref "R5") (pin "2") (pinfunction "2_2") (pintype "passive"))
      (node (ref "RL1") (pin "5") (pinfunction "5_5") (pintype "passive"))
    )
    (net (code "38") (name "Net-(D2-A)") (class "Default")
      (node (ref "D2") (pin "1") (pinfunction "A_1") (pintype "passive"))
      (node (ref "Q2") (pin "2") (pinfunction "C_2") (pintype "passive"))
      (node (ref "R6") (pin "2") (pinfunction "2_2") (pintype "passive"))
      (node (ref "RL2") (pin "5") (pinfunction "5_5") (pintype "passive"))
    )
    (net (code "39") (name "Net-(D3-A)") (class "Default")
      (node (ref "D3") (pin "1") (pinfunction "A_1") (pintype "passive"))
      (node (ref "Q3") (pin "2") (pinfunction "C_2") (pintype "passive"))
      (node (ref "R17") (pin "2") (pinfunction "2_2") (pintype "passive"))
      (node (ref "RL3") (pin "5") (pinfunction "5_5") (pintype "passive"))
    )
    (net (code "40") (name "Net-(D4-A)") (class "Default")
      (node (ref "D4") (pin "1") (pinfunction "A_1") (pintype "passive"))
      (node (ref "Q4") (pin "2") (pinfunction "C_2") (pintype "passive"))
      (node (ref "R18") (pin "2") (pinfunction "2_2") (pintype "passive"))
      (node (ref "RL4") (pin "5") (pinfunction "5_5") (pintype "passive"))
    )
    (net (code "41") (name "Net-(D5-A)") (class "Default")
      (node (ref "D5") (pin "1") (pinfunction "A_1") (pintype "passive"))
      (node (ref "Q5") (pin "2") (pinfunction "C_2") (pintype "passive"))
      (node (ref "R29") (pin "2") (pinfunction "2_2") (pintype "passive"))
      (node (ref "RL5") (pin "5") (pinfunction "5_5") (pintype "passive"))
    )
    (net (code "42") (name "Net-(D6-A)") (class "Default")
      (node (ref "D6") (pin "1") (pinfunction "A_1") (pintype "passive"))
      (node (ref "Q6") (pin "2") (pinfunction "C_2") (pintype "passive"))
      (node (ref "R32") (pin "2") (pinfunction "2_2") (pintype "passive"))
      (node (ref "RL6") (pin "5") (pinfunction "5_5") (pintype "passive"))
    )
    (net (code "43") (name "Net-(D7-A)") (class "Default")
      (node (ref "D7") (pin "1") (pinfunction "A_1") (pintype "passive"))
      (node (ref "Q7") (pin "2") (pinfunction "C_2") (pintype "passive"))
      (node (ref "R40") (pin "2") (pinfunction "2_2") (pintype "passive"))
      (node (ref "RL7") (pin "5") (pinfunction "5_5") (pintype "passive"))
    )
    (net (code "44") (name "Net-(LED1-K)") (class "Default")
      (node (ref "LED1") (pin "2") (pinfunction "K_2") (pintype "passive"))
      (node (ref "R3") (pin "2") (pinfunction "2_2") (pintype "passive"))
    )
    (net (code "45") (name "Net-(LED2-K)") (class "Default")
      (node (ref "LED2") (pin "2") (pinfunction "K_2") (pintype "passive"))
      (node (ref "R4") (pin "2") (pinfunction "2_2") (pintype "passive"))
    )
    (net (code "46") (name "Net-(LED3-K)") (class "Default")
      (node (ref "LED3") (pin "2") (pinfunction "K_2") (pintype "passive"))
      (node (ref "R5") (pin "1") (pinfunction "1_1") (pintype "passive"))
    )
    (net (code "47") (name "Net-(LED4-K)") (class "Default")
      (node (ref "LED4") (pin "2") (pinfunction "K_2") (pintype "passive"))
      (node (ref "R6") (pin "1") (pinfunction "1_1") (pintype "passive"))
    )
    (net (code "48") (name "Net-(LED5-K)") (class "Default")
      (node (ref "LED5") (pin "2") (pinfunction "K_2") (pintype "passive"))
      (node (ref "R15") (pin "2") (pinfunction "2_2") (pintype "passive"))
    )
    (net (code "49") (name "Net-(LED6-K)") (class "Default")
      (node (ref "LED6") (pin "2") (pinfunction "K_2") (pintype "passive"))
      (node (ref "R16") (pin "2") (pinfunction "2_2") (pintype "passive"))
    )
    (net (code "50") (name "Net-(LED7-K)") (class "Default")
      (node (ref "LED7") (pin "2") (pinfunction "K_2") (pintype "passive"))
      (node (ref "R17") (pin "1") (pinfunction "1_1") (pintype "passive"))
    )
    (net (code "51") (name "Net-(LED8-K)") (class "Default")
      (node (ref "LED8") (pin "2") (pinfunction "K_2") (pintype "passive"))
      (node (ref "R18") (pin "1") (pinfunction "1_1") (pintype "passive"))
    )
    (net (code "52") (name "Net-(LED9-K)") (class "Default")
      (node (ref "LED9") (pin "2") (pinfunction "K_2") (pintype "passive"))
      (node (ref "R27") (pin "2") (pinfunction "2_2") (pintype "passive"))
    )
    (net (code "53") (name "Net-(LED10-K)") (class "Default")
      (node (ref "LED10") (pin "2") (pinfunction "K_2") (pintype "passive"))
      (node (ref "R28") (pin "2") (pinfunction "2_2") (pintype "passive"))
    )
    (net (code "54") (name "Net-(LED11-K)") (class "Default")
      (node (ref "LED11") (pin "2") (pinfunction "K_2") (pintype "passive"))
      (node (ref "R29") (pin "1") (pinfunction "1_1") (pintype "passive"))
    )
    (net (code "55") (name "Net-(LED12-K)") (class "Default")
      (node (ref "LED12") (pin "2") (pinfunction "K_2") (pintype "passive"))
      (node (ref "R32") (pin "1") (pinfunction "1_1") (pintype "passive"))
    )
    (net (code "56") (name "Net-(LED13-K)") (class "Default")
      (node (ref "LED13") (pin "2") (pinfunction "K_2") (pintype "passive"))
      (node (ref "R38") (pin "2") (pinfunction "2_2") (pintype "passive"))
    )
    (net (code "57") (name "Net-(LED14-K)") (class "Default")
      (node (ref "LED14") (pin "2") (pinfunction "K_2") (pintype "passive"))
      (node (ref "R40") (pin "1") (pinfunction "1_1") (pintype "passive"))
    )
    (net (code "58") (name "Net-(Q1-B)") (class "Default")
      (node (ref "Q1") (pin "3") (pinfunction "B_3") (pintype "passive"))
      (node (ref "R11") (pin "2") (pinfunction "2_2") (pintype "passive"))
    )
    (net (code "59") (name "Net-(Q2-B)") (class "Default")
      (node (ref "Q2") (pin "3") (pinfunction "B_3") (pintype "passive"))
      (node (ref "R12") (pin "2") (pinfunction "2_2") (pintype "passive"))
    )
    (net (code "60") (name "Net-(Q3-B)") (class "Default")
      (node (ref "Q3") (pin "3") (pinfunction "B_3") (pintype "passive"))
      (node (ref "R23") (pin "2") (pinfunction "2_2") (pintype "passive"))
    )
    (net (code "61") (name "Net-(Q4-B)") (class "Default")
      (node (ref "Q4") (pin "3") (pinfunction "B_3") (pintype "passive"))
      (node (ref "R24") (pin "2") (pinfunction "2_2") (pintype "passive"))
    )
    (net (code "62") (name "Net-(Q5-B)") (class "Default")
      (node (ref "Q5") (pin "3") (pinfunction "B_3") (pintype "passive"))
      (node (ref "R35") (pin "2") (pinfunction "2_2") (pintype "passive"))
    )
    (net (code "63") (name "Net-(Q6-B)") (class "Default")
      (node (ref "Q6") (pin "3") (pinfunction "B_3") (pintype "passive"))
      (node (ref "R36") (pin "2") (pinfunction "2_2") (pintype "passive"))
    )
    (net (code "64") (name "Net-(Q7-B)") (class "Default")
      (node (ref "Q7") (pin "3") (pinfunction "B_3") (pintype "passive"))
      (node (ref "R42") (pin "2") (pinfunction "2_2") (pintype "passive"))
    )
    (net (code "65") (name "Net-(U1-A)") (class "Default")
      (node (ref "R9") (pin "2") (pinfunction "2_2") (pintype "passive"))
      (node (ref "U1") (pin "1") (pinfunction "A_1") (pintype "passive"))
    )
    (net (code "66") (name "Net-(U1-E)") (class "Default")
      (node (ref "R11") (pin "1") (pinfunction "1_1") (pintype "passive"))
      (node (ref "U1") (pin "3") (pinfunction "E_3") (pintype "passive"))
    )
    (net (code "67") (name "Net-(U2-A)") (class "Default")
      (node (ref "R10") (pin "2") (pinfunction "2_2") (pintype "passive"))
      (node (ref "U2") (pin "1") (pinfunction "A_1") (pintype "passive"))
    )
    (net (code "68") (name "Net-(U2-E)") (class "Default")
      (node (ref "R12") (pin "1") (pinfunction "1_1") (pintype "passive"))
      (node (ref "U2") (pin "3") (pinfunction "E_3") (pintype "passive"))
    )
    (net (code "69") (name "Net-(U3-A)") (class "Default")
      (node (ref "R21") (pin "2") (pinfunction "2_2") (pintype "passive"))
      (node (ref "U3") (pin "1") (pinfunction "A_1") (pintype "passive"))
    )
    (net (code "70") (name "Net-(U3-E)") (class "Default")
      (node (ref "R23") (pin "1") (pinfunction "1_1") (pintype "passive"))
      (node (ref "U3") (pin "3") (pinfunction "E_3") (pintype "passive"))
    )
    (net (code "71") (name "Net-(U4-A)") (class "Default")
      (node (ref "R22") (pin "2") (pinfunction "2_2") (pintype "passive"))
      (node (ref "U4") (pin "1") (pinfunction "A_1") (pintype "passive"))
    )
    (net (code "72") (name "Net-(U4-E)") (class "Default")
      (node (ref "R24") (pin "1") (pinfunction "1_1") (pintype "passive"))
      (node (ref "U4") (pin "3") (pinfunction "E_3") (pintype "passive"))
    )
    (net (code "73") (name "Net-(U5-A)") (class "Default")
      (node (ref "R33") (pin "2") (pinfunction "2_2") (pintype "passive"))
      (node (ref "U5") (pin "1") (pinfunction "A_1") (pintype "passive"))
    )
    (net (code "74") (name "Net-(U5-E)") (class "Default")
      (node (ref "R35") (pin "1") (pinfunction "1_1") (pintype "passive"))
      (node (ref "U5") (pin "3") (pinfunction "E_3") (pintype "passive"))
    )
    (net (code "75") (name "Net-(U6-A)") (class "Default")
      (node (ref "R34") (pin "2") (pinfunction "2_2") (pintype "passive"))
      (node (ref "U6") (pin "1") (pinfunction "A_1") (pintype "passive"))
    )
    (net (code "76") (name "Net-(U6-E)") (class "Default")
      (node (ref "R36") (pin "1") (pinfunction "1_1") (pintype "passive"))
      (node (ref "U6") (pin "3") (pinfunction "E_3") (pintype "passive"))
    )
    (net (code "77") (name "Net-(U8-A)") (class "Default")
      (node (ref "R41") (pin "2") (pinfunction "2_2") (pintype "passive"))
      (node (ref "U8") (pin "1") (pinfunction "A_1") (pintype "passive"))
    )
    (net (code "78") (name "Net-(U8-E)") (class "Default")
      (node (ref "R42") (pin "1") (pinfunction "1_1") (pintype "passive"))
      (node (ref "U8") (pin "3") (pinfunction "E_3") (pintype "passive"))
    )
    (net (code "79") (name "VCC5") (class "Default")
      (node (ref "B1") (pin "2") (pinfunction "VIN_2") (pintype "passive"))
      (node (ref "BUCK LM1") (pin "4") (pinfunction "OUT+_4") (pintype "passive"))
      (node (ref "C5") (pin "1") (pinfunction "1_1") (pintype "passive"))
      (node (ref "D1") (pin "2") (pinfunction "K_2") (pintype "passive"))
      (node (ref "D2") (pin "2") (pinfunction "K_2") (pintype "passive"))
      (node (ref "D3") (pin "2") (pinfunction "K_2") (pintype "passive"))
      (node (ref "D4") (pin "2") (pinfunction "K_2") (pintype "passive"))
      (node (ref "D5") (pin "2") (pinfunction "K_2") (pintype "passive"))
      (node (ref "D6") (pin "2") (pinfunction "K_2") (pintype "passive"))
      (node (ref "D7") (pin "2") (pinfunction "K_2") (pintype "passive"))
      (node (ref "LED11") (pin "1") (pinfunction "A_1") (pintype "passive"))
      (node (ref "LED12") (pin "1") (pinfunction "A_1") (pintype "passive"))
      (node (ref "LED14") (pin "1") (pinfunction "A_1") (pintype "passive"))
      (node (ref "LED3") (pin "1") (pinfunction "A_1") (pintype "passive"))
      (node (ref "LED4") (pin "1") (pinfunction "A_1") (pintype "passive"))
      (node (ref "LED7") (pin "1") (pinfunction "A_1") (pintype "passive"))
      (node (ref "LED8") (pin "1") (pinfunction "A_1") (pintype "passive"))
      (node (ref "RL1") (pin "3") (pinfunction "3_3") (pintype "passive"))
      (node (ref "RL2") (pin "3") (pinfunction "3_3") (pintype "passive"))
      (node (ref "RL3") (pin "3") (pinfunction "3_3") (pintype "passive"))
      (node (ref "RL4") (pin "3") (pinfunction "3_3") (pintype "passive"))
      (node (ref "RL5") (pin "3") (pinfunction "3_3") (pintype "passive"))
      (node (ref "RL6") (pin "3") (pinfunction "3_3") (pintype "passive"))
      (node (ref "RL7") (pin "3") (pinfunction "3_3") (pintype "passive"))
      (node (ref "U1") (pin "4") (pinfunction "C_4") (pintype "passive"))
      (node (ref "U2") (pin "4") (pinfunction "C_4") (pintype "passive"))
      (node (ref "U3") (pin "4") (pinfunction "C_4") (pintype "passive"))
      (node (ref "U4") (pin "4") (pinfunction "C_4") (pintype "passive"))
      (node (ref "U5") (pin "4") (pinfunction "C_4") (pintype "passive"))
      (node (ref "U6") (pin "4") (pinfunction "C_4") (pintype "passive"))
      (node (ref "U8") (pin "4") (pinfunction "C_4") (pintype "passive"))
    )
    (net (code "80") (name "VCC5_ISO") (class "Default")
      (node (ref "B1") (pin "4") (pinfunction "+VO_4") (pintype "passive"))
      (node (ref "C11") (pin "4") (pinfunction "4_4") (pintype "passive"))
      (node (ref "C12") (pin "3") (pinfunction "3_3") (pintype "passive"))
      (node (ref "C4") (pin "1") (pinfunction "1_1") (pintype "passive"))
      (node (ref "LED1") (pin "1") (pinfunction "A_1") (pintype "passive"))
      (node (ref "LED10") (pin "1") (pinfunction "A_1") (pintype "passive"))
      (node (ref "LED13") (pin "1") (pinfunction "A_1") (pintype "passive"))
      (node (ref "LED2") (pin "1") (pinfunction "A_1") (pintype "passive"))
      (node (ref "LED5") (pin "1") (pinfunction "A_1") (pintype "passive"))
      (node (ref "LED6") (pin "1") (pinfunction "A_1") (pintype "passive"))
      (node (ref "LED9") (pin "1") (pinfunction "A_1") (pintype "passive"))
      (node (ref "R1") (pin "2") (pinfunction "2_2") (pintype "passive"))
      (node (ref "R13") (pin "2") (pinfunction "2_2") (pintype "passive"))
      (node (ref "R14") (pin "2") (pinfunction "2_2") (pintype "passive"))
      (node (ref "R2") (pin "2") (pinfunction "2_2") (pintype "passive"))
      (node (ref "R25") (pin "2") (pinfunction "2_2") (pintype "passive"))
      (node (ref "R26") (pin "2") (pinfunction "2_2") (pintype "passive"))
      (node (ref "R37") (pin "2") (pinfunction "2_2") (pintype "passive"))
      (node (ref "U7") (pin "15") (pinfunction "VIN_15") (pintype "passive"))
    )
    (net (code "81") (name "VCC33_ISO") (class "Default")
      (node (ref "C8") (pin "3") (pinfunction "3_3") (pintype "passive"))
      (node (ref "U7") (pin "16") (pinfunction "3V3_16") (pintype "passive"))
    )
    (net (code "82") (name "VCC_IN") (class "Default")
      (node (ref "BUCK LM1") (pin "1") (pinfunction "IN+_1") (pintype "passive"))
      (node (ref "C1") (pin "2") (pinfunction "2_2") (pintype "passive"))
    )
    (net (code "84") (name "unconnected-(RL1-Pad2)") (class "Default")
      (node (ref "RL1") (pin "2") (pinfunction "2_2") (pintype "passive+no_connect"))
    )
    (net (code "85") (name "unconnected-(RL2-Pad2)") (class "Default")
      (node (ref "RL2") (pin "2") (pinfunction "2_2") (pintype "passive+no_connect"))
    )
    (net (code "86") (name "unconnected-(RL3-Pad2)") (class "Default")
      (node (ref "RL3") (pin "2") (pinfunction "2_2") (pintype "passive+no_connect"))
    )
    (net (code "87") (name "unconnected-(RL4-Pad2)") (class "Default")
      (node (ref "RL4") (pin "2") (pinfunction "2_2") (pintype "passive+no_connect"))
    )
    (net (code "88") (name "unconnected-(RL5-Pad2)") (class "Default")
      (node (ref "RL5") (pin "2") (pinfunction "2_2") (pintype "passive+no_connect"))
    )
    (net (code "89") (name "unconnected-(RL6-Pad2)") (class "Default")
      (node (ref "RL6") (pin "2") (pinfunction "2_2") (pintype "passive+no_connect"))
    )
    (net (code "90") (name "unconnected-(RL7-Pad2)") (class "Default")
      (node (ref "RL7") (pin "2") (pinfunction "2_2") (pintype "passive+no_connect"))
    )
    (net (code "91") (name "unconnected-(U7-D2-Pad19)") (class "Default")
      (node (ref "U7") (pin "19") (pinfunction "D2_19") (pintype "passive+no_connect"))
    )
    (net (code "92") (name "unconnected-(U7-D34-Pad4)") (class "Default")
      (node (ref "U7") (pin "4") (pinfunction "D34_4") (pintype "passive+no_connect"))
    )
    (net (code "93") (name "unconnected-(U7-D35-Pad5)") (class "Default")
      (node (ref "U7") (pin "5") (pinfunction "D35_5") (pintype "passive+no_connect"))
    )
    (net (code "94") (name "unconnected-(U7-EN-Pad1)") (class "Default")
      (node (ref "U7") (pin "1") (pinfunction "EN_1") (pintype "passive+no_connect"))
    )
    (net (code "95") (name "unconnected-(U7-GND-Pad17)") (class "Default")
      (node (ref "U7") (pin "17") (pinfunction "GND_17") (pintype "passive+no_connect"))
    )
    (net (code "96") (name "unconnected-(U7-RX0-Pad27)") (class "Default")
      (node (ref "U7") (pin "27") (pinfunction "RX0_27") (pintype "passive+no_connect"))
    )
    (net (code "97") (name "unconnected-(U7-TX0-Pad28)") (class "Default")
      (node (ref "U7") (pin "28") (pinfunction "TX0_28") (pintype "passive+no_connect"))
    )
    (net (code "98") (name "unconnected-(U7-VN-Pad3)") (class "Default")
      (node (ref "U7") (pin "3") (pinfunction "VN_3") (pintype "passive+no_connect"))
    )
  )
)
